# SCH_Funkypad.net
KiCad netlist of a schematic drawn in EasyEDA
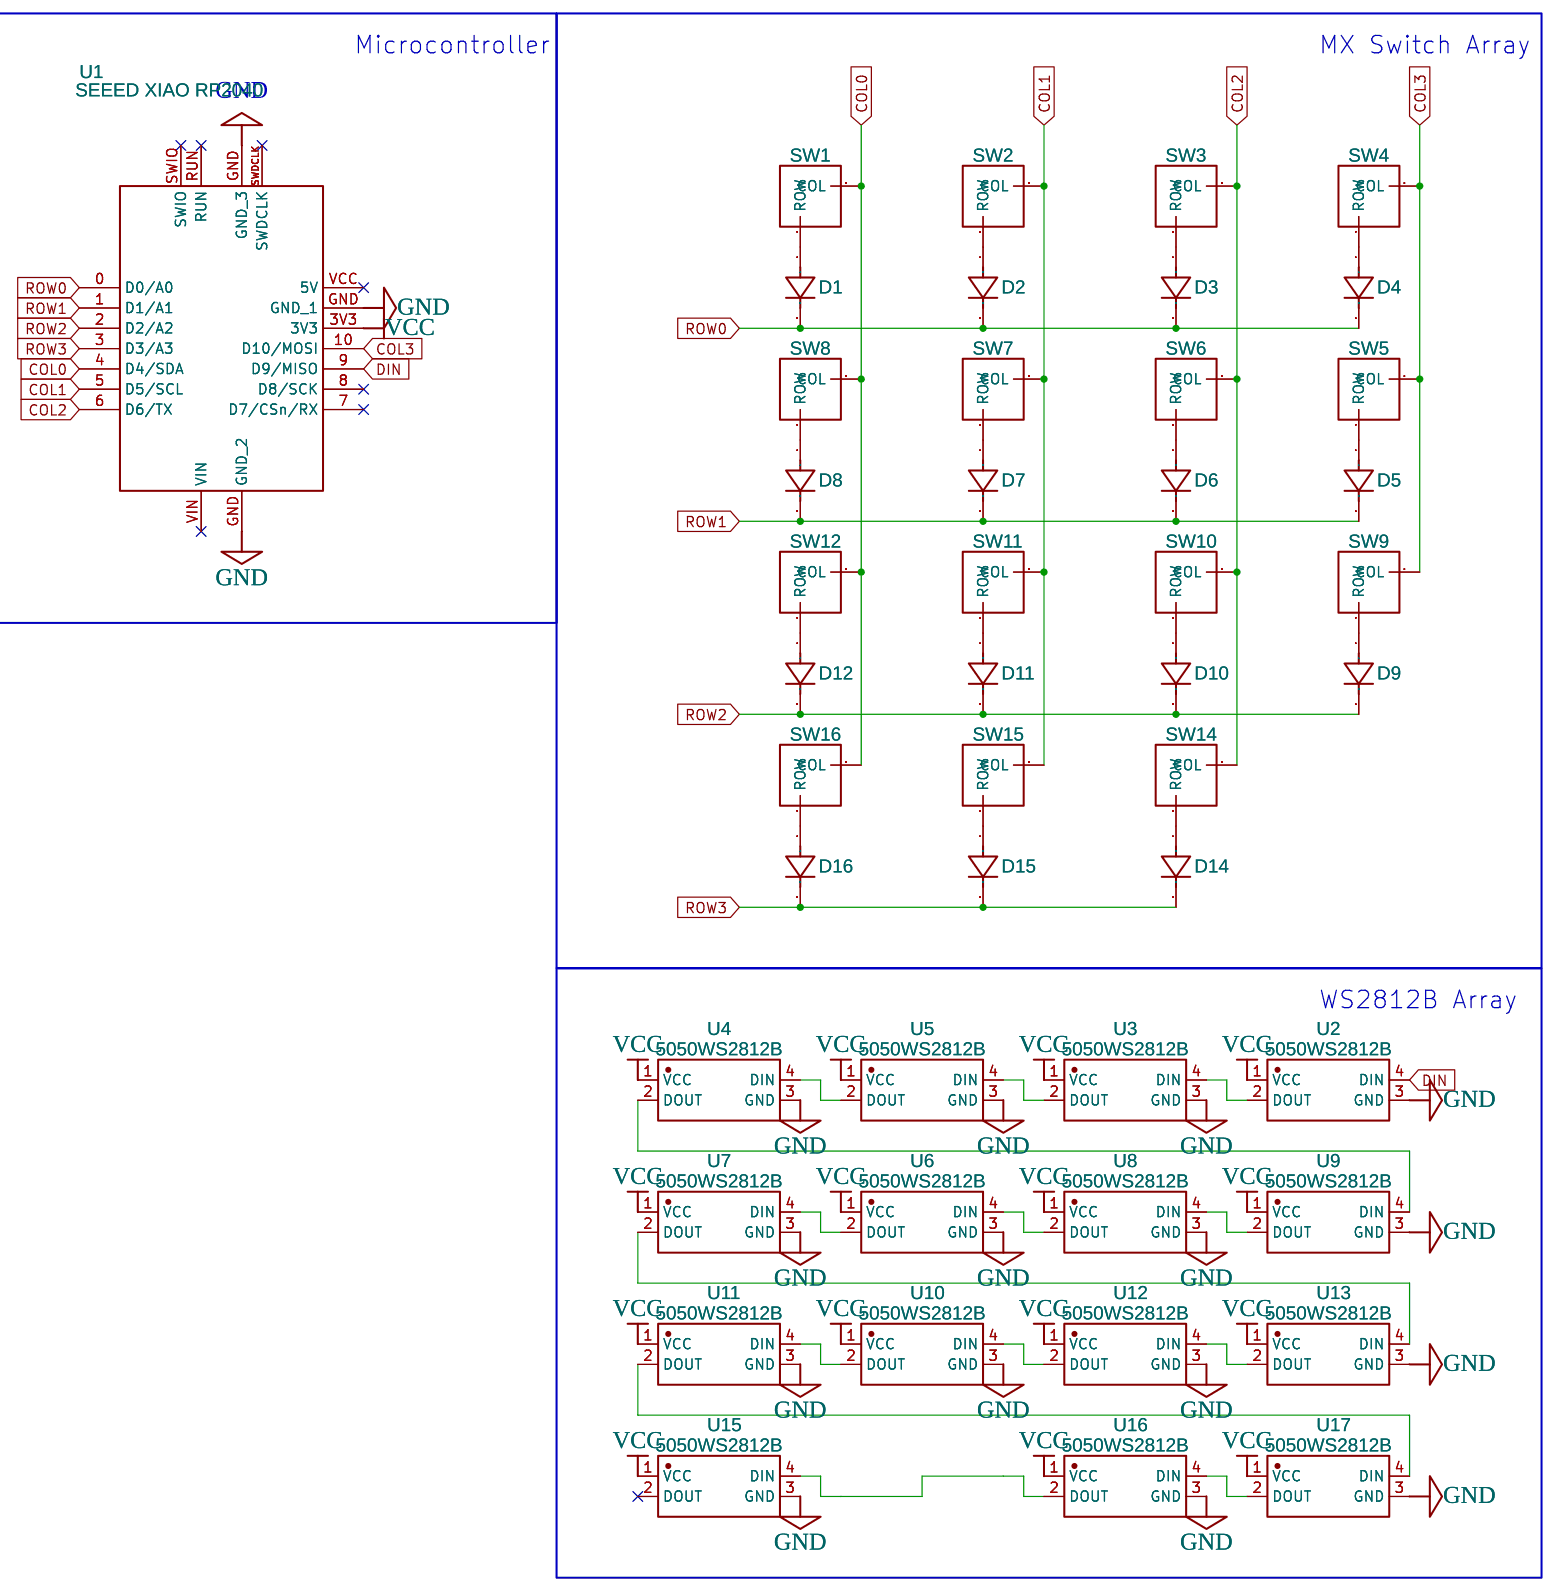
[diagram p0: schematic sheet]

(export (version "E")
  (design (tool "Eeschema 10.0.6"))
  (components
    (comp (ref "D1")
      (value "1N4148_C18195411")
      (fields (field (name "Manufacturer Part") "1N4148") (field (name "Manufacturer") "LJ(朗捷)"))
      (libsource (lib "") (part "1N4148_C18195411"))
    )
    (comp (ref "D2")
      (value "1N4148_C18195411")
      (fields (field (name "Manufacturer Part") "1N4148") (field (name "Manufacturer") "LJ(朗捷)"))
      (libsource (lib "") (part "1N4148_C18195411"))
    )
    (comp (ref "D3")
      (value "1N4148_C18195411")
      (fields (field (name "Manufacturer Part") "1N4148") (field (name "Manufacturer") "LJ(朗捷)"))
      (libsource (lib "") (part "1N4148_C18195411"))
    )
    (comp (ref "D4")
      (value "1N4148_C18195411")
      (fields (field (name "Manufacturer Part") "1N4148") (field (name "Manufacturer") "LJ(朗捷)"))
      (libsource (lib "") (part "1N4148_C18195411"))
    )
    (comp (ref "D5")
      (value "1N4148_C18195411")
      (fields (field (name "Manufacturer Part") "1N4148") (field (name "Manufacturer") "LJ(朗捷)"))
      (libsource (lib "") (part "1N4148_C18195411"))
    )
    (comp (ref "D6")
      (value "1N4148_C18195411")
      (fields (field (name "Manufacturer Part") "1N4148") (field (name "Manufacturer") "LJ(朗捷)"))
      (libsource (lib "") (part "1N4148_C18195411"))
    )
    (comp (ref "D7")
      (value "1N4148_C18195411")
      (fields (field (name "Manufacturer Part") "1N4148") (field (name "Manufacturer") "LJ(朗捷)"))
      (libsource (lib "") (part "1N4148_C18195411"))
    )
    (comp (ref "D8")
      (value "1N4148_C18195411")
      (fields (field (name "Manufacturer Part") "1N4148") (field (name "Manufacturer") "LJ(朗捷)"))
      (libsource (lib "") (part "1N4148_C18195411"))
    )
    (comp (ref "D9")
      (value "1N4148_C18195411")
      (fields (field (name "Manufacturer Part") "1N4148") (field (name "Manufacturer") "LJ(朗捷)"))
      (libsource (lib "") (part "1N4148_C18195411"))
    )
    (comp (ref "D10")
      (value "1N4148_C18195411")
      (fields (field (name "Manufacturer Part") "1N4148") (field (name "Manufacturer") "LJ(朗捷)"))
      (libsource (lib "") (part "1N4148_C18195411"))
    )
    (comp (ref "D11")
      (value "1N4148_C18195411")
      (fields (field (name "Manufacturer Part") "1N4148") (field (name "Manufacturer") "LJ(朗捷)"))
      (libsource (lib "") (part "1N4148_C18195411"))
    )
    (comp (ref "D12")
      (value "1N4148_C18195411")
      (fields (field (name "Manufacturer Part") "1N4148") (field (name "Manufacturer") "LJ(朗捷)"))
      (libsource (lib "") (part "1N4148_C18195411"))
    )
    (comp (ref "D14")
      (value "1N4148_C18195411")
      (fields (field (name "Manufacturer Part") "1N4148") (field (name "Manufacturer") "LJ(朗捷)"))
      (libsource (lib "") (part "1N4148_C18195411"))
    )
    (comp (ref "D15")
      (value "1N4148_C18195411")
      (fields (field (name "Manufacturer Part") "1N4148") (field (name "Manufacturer") "LJ(朗捷)"))
      (libsource (lib "") (part "1N4148_C18195411"))
    )
    (comp (ref "D16")
      (value "1N4148_C18195411")
      (fields (field (name "Manufacturer Part") "1N4148") (field (name "Manufacturer") "LJ(朗捷)"))
      (libsource (lib "") (part "1N4148_C18195411"))
    )
    (comp (ref "SW1")
      (value "CHERRY MX SWITCH 1.0U")
      (fields (field (name "Manufacturer Part") "Cherry"))
      (libsource (lib "") (part "CHERRY MX SWITCH 1.0U"))
    )
    (comp (ref "SW2")
      (value "CHERRY MX SWITCH 1.0U")
      (fields (field (name "Manufacturer Part") "Cherry"))
      (libsource (lib "") (part "CHERRY MX SWITCH 1.0U"))
    )
    (comp (ref "SW3")
      (value "CHERRY MX SWITCH 1.0U")
      (fields (field (name "Manufacturer Part") "Cherry"))
      (libsource (lib "") (part "CHERRY MX SWITCH 1.0U"))
    )
    (comp (ref "SW4")
      (value "CHERRY MX SWITCH 1.0U")
      (fields (field (name "Manufacturer Part") "Cherry"))
      (libsource (lib "") (part "CHERRY MX SWITCH 1.0U"))
    )
    (comp (ref "SW5")
      (value "CHERRY MX SWITCH 1.0U")
      (fields (field (name "Manufacturer Part") "Cherry"))
      (libsource (lib "") (part "CHERRY MX SWITCH 1.0U"))
    )
    (comp (ref "SW6")
      (value "CHERRY MX SWITCH 1.0U")
      (fields (field (name "Manufacturer Part") "Cherry"))
      (libsource (lib "") (part "CHERRY MX SWITCH 1.0U"))
    )
    (comp (ref "SW7")
      (value "CHERRY MX SWITCH 1.0U")
      (fields (field (name "Manufacturer Part") "Cherry"))
      (libsource (lib "") (part "CHERRY MX SWITCH 1.0U"))
    )
    (comp (ref "SW8")
      (value "CHERRY MX SWITCH 1.0U")
      (fields (field (name "Manufacturer Part") "Cherry"))
      (libsource (lib "") (part "CHERRY MX SWITCH 1.0U"))
    )
    (comp (ref "SW9")
      (value "CHERRY MX SWITCH 1.0U")
      (fields (field (name "Manufacturer Part") "Cherry"))
      (libsource (lib "") (part "CHERRY MX SWITCH 1.0U"))
    )
    (comp (ref "SW10")
      (value "CHERRY MX SWITCH 1.0U")
      (fields (field (name "Manufacturer Part") "Cherry"))
      (libsource (lib "") (part "CHERRY MX SWITCH 1.0U"))
    )
    (comp (ref "SW11")
      (value "CHERRY MX SWITCH 1.0U")
      (fields (field (name "Manufacturer Part") "Cherry"))
      (libsource (lib "") (part "CHERRY MX SWITCH 1.0U"))
    )
    (comp (ref "SW12")
      (value "CHERRY MX SWITCH 1.0U")
      (fields (field (name "Manufacturer Part") "Cherry"))
      (libsource (lib "") (part "CHERRY MX SWITCH 1.0U"))
    )
    (comp (ref "SW14")
      (value "CHERRY MX SWITCH 1.0U")
      (fields (field (name "Manufacturer Part") "Cherry"))
      (libsource (lib "") (part "CHERRY MX SWITCH 1.0U"))
    )
    (comp (ref "SW15")
      (value "CHERRY MX SWITCH 1.0U")
      (fields (field (name "Manufacturer Part") "Cherry"))
      (libsource (lib "") (part "CHERRY MX SWITCH 1.0U"))
    )
    (comp (ref "SW16")
      (value "CHERRY MX SWITCH 1.0U")
      (fields (field (name "Manufacturer Part") "Cherry"))
      (libsource (lib "") (part "CHERRY MX SWITCH 1.0U"))
    )
    (comp (ref "U1") (value "SEEED XIAO RP2040") (libsource (lib "") (part "SEEED XIAO RP2040")))
    (comp (ref "U2") (value "5050WS2812B") (libsource (lib "") (part "5050WS2812B")))
    (comp (ref "U3") (value "5050WS2812B") (libsource (lib "") (part "5050WS2812B")))
    (comp (ref "U4") (value "5050WS2812B") (libsource (lib "") (part "5050WS2812B")))
    (comp (ref "U5") (value "5050WS2812B") (libsource (lib "") (part "5050WS2812B")))
    (comp (ref "U6") (value "5050WS2812B") (libsource (lib "") (part "5050WS2812B")))
    (comp (ref "U7") (value "5050WS2812B") (libsource (lib "") (part "5050WS2812B")))
    (comp (ref "U8") (value "5050WS2812B") (libsource (lib "") (part "5050WS2812B")))
    (comp (ref "U9") (value "5050WS2812B") (libsource (lib "") (part "5050WS2812B")))
    (comp (ref "U10") (value "5050WS2812B") (libsource (lib "") (part "5050WS2812B")))
    (comp (ref "U11") (value "5050WS2812B") (libsource (lib "") (part "5050WS2812B")))
    (comp (ref "U12") (value "5050WS2812B") (libsource (lib "") (part "5050WS2812B")))
    (comp (ref "U13") (value "5050WS2812B") (libsource (lib "") (part "5050WS2812B")))
    (comp (ref "U15") (value "5050WS2812B") (libsource (lib "") (part "5050WS2812B")))
    (comp (ref "U16") (value "5050WS2812B") (libsource (lib "") (part "5050WS2812B")))
    (comp (ref "U17") (value "5050WS2812B") (libsource (lib "") (part "5050WS2812B")))
  )
  (nets
    (net (code "1") (name "COL0") (class "Default")
      (node (ref "SW1") (pin "C") (pinfunction "COL_C") (pintype "unspecified"))
      (node (ref "SW12") (pin "C") (pinfunction "COL_C") (pintype "unspecified"))
      (node (ref "SW16") (pin "C") (pinfunction "COL_C") (pintype "unspecified"))
      (node (ref "SW8") (pin "C") (pinfunction "COL_C") (pintype "unspecified"))
      (node (ref "U1") (pin "4") (pinfunction "D4/SDA_4") (pintype "unspecified"))
    )
    (net (code "2") (name "COL1") (class "Default")
      (node (ref "SW11") (pin "C") (pinfunction "COL_C") (pintype "unspecified"))
      (node (ref "SW15") (pin "C") (pinfunction "COL_C") (pintype "unspecified"))
      (node (ref "SW2") (pin "C") (pinfunction "COL_C") (pintype "unspecified"))
      (node (ref "SW7") (pin "C") (pinfunction "COL_C") (pintype "unspecified"))
      (node (ref "U1") (pin "5") (pinfunction "D5/SCL_5") (pintype "unspecified"))
    )
    (net (code "3") (name "COL2") (class "Default")
      (node (ref "SW10") (pin "C") (pinfunction "COL_C") (pintype "unspecified"))
      (node (ref "SW14") (pin "C") (pinfunction "COL_C") (pintype "unspecified"))
      (node (ref "SW3") (pin "C") (pinfunction "COL_C") (pintype "unspecified"))
      (node (ref "SW6") (pin "C") (pinfunction "COL_C") (pintype "unspecified"))
      (node (ref "U1") (pin "6") (pinfunction "D6/TX_6") (pintype "unspecified"))
    )
    (net (code "4") (name "COL3") (class "Default")
      (node (ref "SW4") (pin "C") (pinfunction "COL_C") (pintype "unspecified"))
      (node (ref "SW5") (pin "C") (pinfunction "COL_C") (pintype "unspecified"))
      (node (ref "SW9") (pin "C") (pinfunction "COL_C") (pintype "unspecified"))
      (node (ref "U1") (pin "10") (pinfunction "D10/MOSI_10") (pintype "unspecified"))
    )
    (net (code "5") (name "DIN") (class "Default")
      (node (ref "U1") (pin "9") (pinfunction "D9/MISO_9") (pintype "unspecified"))
      (node (ref "U2") (pin "4") (pinfunction "DIN_4") (pintype "unspecified"))
    )
    (net (code "6") (name "GND") (class "Default")
      (node (ref "U1") (pin "GND") (pinfunction "GND_2_GND") (pintype "unspecified"))
      (node (ref "U10") (pin "3") (pinfunction "GND_3") (pintype "unspecified"))
      (node (ref "U11") (pin "3") (pinfunction "GND_3") (pintype "unspecified"))
      (node (ref "U12") (pin "3") (pinfunction "GND_3") (pintype "unspecified"))
      (node (ref "U13") (pin "3") (pinfunction "GND_3") (pintype "unspecified"))
      (node (ref "U15") (pin "3") (pinfunction "GND_3") (pintype "unspecified"))
      (node (ref "U16") (pin "3") (pinfunction "GND_3") (pintype "unspecified"))
      (node (ref "U17") (pin "3") (pinfunction "GND_3") (pintype "unspecified"))
      (node (ref "U2") (pin "3") (pinfunction "GND_3") (pintype "unspecified"))
      (node (ref "U3") (pin "3") (pinfunction "GND_3") (pintype "unspecified"))
      (node (ref "U4") (pin "3") (pinfunction "GND_3") (pintype "unspecified"))
      (node (ref "U5") (pin "3") (pinfunction "GND_3") (pintype "unspecified"))
      (node (ref "U6") (pin "3") (pinfunction "GND_3") (pintype "unspecified"))
      (node (ref "U7") (pin "3") (pinfunction "GND_3") (pintype "unspecified"))
      (node (ref "U8") (pin "3") (pinfunction "GND_3") (pintype "unspecified"))
      (node (ref "U9") (pin "3") (pinfunction "GND_3") (pintype "unspecified"))
    )
    (net (code "7") (name "Net-(D1-A)") (class "Default")
      (node (ref "D1") (pin "1") (pinfunction "A_1") (pintype "unspecified"))
      (node (ref "SW1") (pin "R") (pinfunction "ROW_R") (pintype "unspecified"))
    )
    (net (code "8") (name "Net-(D2-A)") (class "Default")
      (node (ref "D2") (pin "1") (pinfunction "A_1") (pintype "unspecified"))
      (node (ref "SW2") (pin "R") (pinfunction "ROW_R") (pintype "unspecified"))
    )
    (net (code "9") (name "Net-(D3-A)") (class "Default")
      (node (ref "D3") (pin "1") (pinfunction "A_1") (pintype "unspecified"))
      (node (ref "SW3") (pin "R") (pinfunction "ROW_R") (pintype "unspecified"))
    )
    (net (code "10") (name "Net-(D4-A)") (class "Default")
      (node (ref "D4") (pin "1") (pinfunction "A_1") (pintype "unspecified"))
      (node (ref "SW4") (pin "R") (pinfunction "ROW_R") (pintype "unspecified"))
    )
    (net (code "11") (name "Net-(D5-A)") (class "Default")
      (node (ref "D5") (pin "1") (pinfunction "A_1") (pintype "unspecified"))
      (node (ref "SW5") (pin "R") (pinfunction "ROW_R") (pintype "unspecified"))
    )
    (net (code "12") (name "Net-(D6-A)") (class "Default")
      (node (ref "D6") (pin "1") (pinfunction "A_1") (pintype "unspecified"))
      (node (ref "SW6") (pin "R") (pinfunction "ROW_R") (pintype "unspecified"))
    )
    (net (code "13") (name "Net-(D7-A)") (class "Default")
      (node (ref "D7") (pin "1") (pinfunction "A_1") (pintype "unspecified"))
      (node (ref "SW7") (pin "R") (pinfunction "ROW_R") (pintype "unspecified"))
    )
    (net (code "14") (name "Net-(D8-A)") (class "Default")
      (node (ref "D8") (pin "1") (pinfunction "A_1") (pintype "unspecified"))
      (node (ref "SW8") (pin "R") (pinfunction "ROW_R") (pintype "unspecified"))
    )
    (net (code "15") (name "Net-(D9-A)") (class "Default")
      (node (ref "D9") (pin "1") (pinfunction "A_1") (pintype "unspecified"))
      (node (ref "SW9") (pin "R") (pinfunction "ROW_R") (pintype "unspecified"))
    )
    (net (code "16") (name "Net-(D10-A)") (class "Default")
      (node (ref "D10") (pin "1") (pinfunction "A_1") (pintype "unspecified"))
      (node (ref "SW10") (pin "R") (pinfunction "ROW_R") (pintype "unspecified"))
    )
    (net (code "17") (name "Net-(D11-A)") (class "Default")
      (node (ref "D11") (pin "1") (pinfunction "A_1") (pintype "unspecified"))
      (node (ref "SW11") (pin "R") (pinfunction "ROW_R") (pintype "unspecified"))
    )
    (net (code "18") (name "Net-(D12-A)") (class "Default")
      (node (ref "D12") (pin "1") (pinfunction "A_1") (pintype "unspecified"))
      (node (ref "SW12") (pin "R") (pinfunction "ROW_R") (pintype "unspecified"))
    )
    (net (code "19") (name "Net-(D14-A)") (class "Default")
      (node (ref "D14") (pin "1") (pinfunction "A_1") (pintype "unspecified"))
      (node (ref "SW14") (pin "R") (pinfunction "ROW_R") (pintype "unspecified"))
    )
    (net (code "20") (name "Net-(D15-A)") (class "Default")
      (node (ref "D15") (pin "1") (pinfunction "A_1") (pintype "unspecified"))
      (node (ref "SW15") (pin "R") (pinfunction "ROW_R") (pintype "unspecified"))
    )
    (net (code "21") (name "Net-(D16-A)") (class "Default")
      (node (ref "D16") (pin "1") (pinfunction "A_1") (pintype "unspecified"))
      (node (ref "SW16") (pin "R") (pinfunction "ROW_R") (pintype "unspecified"))
    )
    (net (code "22") (name "Net-(U2-DOUT)") (class "Default")
      (node (ref "U2") (pin "2") (pinfunction "DOUT_2") (pintype "unspecified"))
      (node (ref "U3") (pin "4") (pinfunction "DIN_4") (pintype "unspecified"))
    )
    (net (code "23") (name "Net-(U3-DOUT)") (class "Default")
      (node (ref "U3") (pin "2") (pinfunction "DOUT_2") (pintype "unspecified"))
      (node (ref "U5") (pin "4") (pinfunction "DIN_4") (pintype "unspecified"))
    )
    (net (code "24") (name "Net-(U4-DIN)") (class "Default")
      (node (ref "U4") (pin "4") (pinfunction "DIN_4") (pintype "unspecified"))
      (node (ref "U5") (pin "2") (pinfunction "DOUT_2") (pintype "unspecified"))
    )
    (net (code "25") (name "Net-(U4-DOUT)") (class "Default")
      (node (ref "U4") (pin "2") (pinfunction "DOUT_2") (pintype "unspecified"))
      (node (ref "U9") (pin "4") (pinfunction "DIN_4") (pintype "unspecified"))
    )
    (net (code "26") (name "Net-(U6-DIN)") (class "Default")
      (node (ref "U6") (pin "4") (pinfunction "DIN_4") (pintype "unspecified"))
      (node (ref "U8") (pin "2") (pinfunction "DOUT_2") (pintype "unspecified"))
    )
    (net (code "27") (name "Net-(U6-DOUT)") (class "Default")
      (node (ref "U6") (pin "2") (pinfunction "DOUT_2") (pintype "unspecified"))
      (node (ref "U7") (pin "4") (pinfunction "DIN_4") (pintype "unspecified"))
    )
    (net (code "28") (name "Net-(U8-DIN)") (class "Default")
      (node (ref "U8") (pin "4") (pinfunction "DIN_4") (pintype "unspecified"))
      (node (ref "U9") (pin "2") (pinfunction "DOUT_2") (pintype "unspecified"))
    )
    (net (code "29") (name "Net-(U10-DIN)") (class "Default")
      (node (ref "U10") (pin "4") (pinfunction "DIN_4") (pintype "unspecified"))
      (node (ref "U12") (pin "2") (pinfunction "DOUT_2") (pintype "unspecified"))
    )
    (net (code "30") (name "Net-(U10-DOUT)") (class "Default")
      (node (ref "U10") (pin "2") (pinfunction "DOUT_2") (pintype "unspecified"))
      (node (ref "U11") (pin "4") (pinfunction "DIN_4") (pintype "unspecified"))
    )
    (net (code "31") (name "Net-(U11-DOUT)") (class "Default")
      (node (ref "U11") (pin "2") (pinfunction "DOUT_2") (pintype "unspecified"))
      (node (ref "U17") (pin "4") (pinfunction "DIN_4") (pintype "unspecified"))
    )
    (net (code "32") (name "Net-(U12-DIN)") (class "Default")
      (node (ref "U12") (pin "4") (pinfunction "DIN_4") (pintype "unspecified"))
      (node (ref "U13") (pin "2") (pinfunction "DOUT_2") (pintype "unspecified"))
    )
    (net (code "33") (name "Net-(U13-DIN)") (class "Default")
      (node (ref "U13") (pin "4") (pinfunction "DIN_4") (pintype "unspecified"))
      (node (ref "U7") (pin "2") (pinfunction "DOUT_2") (pintype "unspecified"))
    )
    (net (code "34") (name "Net-(U15-DIN)") (class "Default")
      (node (ref "U15") (pin "4") (pinfunction "DIN_4") (pintype "unspecified"))
      (node (ref "U16") (pin "2") (pinfunction "DOUT_2") (pintype "unspecified"))
    )
    (net (code "35") (name "Net-(U16-DIN)") (class "Default")
      (node (ref "U16") (pin "4") (pinfunction "DIN_4") (pintype "unspecified"))
      (node (ref "U17") (pin "2") (pinfunction "DOUT_2") (pintype "unspecified"))
    )
    (net (code "36") (name "ROW0") (class "Default")
      (node (ref "D1") (pin "2") (pinfunction "C_2") (pintype "unspecified"))
      (node (ref "D2") (pin "2") (pinfunction "C_2") (pintype "unspecified"))
      (node (ref "D3") (pin "2") (pinfunction "C_2") (pintype "unspecified"))
      (node (ref "D4") (pin "2") (pinfunction "C_2") (pintype "unspecified"))
      (node (ref "U1") (pin "0") (pinfunction "D0/A0_0") (pintype "unspecified"))
    )
    (net (code "37") (name "ROW1") (class "Default")
      (node (ref "D5") (pin "2") (pinfunction "C_2") (pintype "unspecified"))
      (node (ref "D6") (pin "2") (pinfunction "C_2") (pintype "unspecified"))
      (node (ref "D7") (pin "2") (pinfunction "C_2") (pintype "unspecified"))
      (node (ref "D8") (pin "2") (pinfunction "C_2") (pintype "unspecified"))
      (node (ref "U1") (pin "1") (pinfunction "D1/A1_1") (pintype "unspecified"))
    )
    (net (code "38") (name "ROW2") (class "Default")
      (node (ref "D10") (pin "2") (pinfunction "C_2") (pintype "unspecified"))
      (node (ref "D11") (pin "2") (pinfunction "C_2") (pintype "unspecified"))
      (node (ref "D12") (pin "2") (pinfunction "C_2") (pintype "unspecified"))
      (node (ref "D9") (pin "2") (pinfunction "C_2") (pintype "unspecified"))
      (node (ref "U1") (pin "2") (pinfunction "D2/A2_2") (pintype "unspecified"))
    )
    (net (code "39") (name "ROW3") (class "Default")
      (node (ref "D14") (pin "2") (pinfunction "C_2") (pintype "unspecified"))
      (node (ref "D15") (pin "2") (pinfunction "C_2") (pintype "unspecified"))
      (node (ref "D16") (pin "2") (pinfunction "C_2") (pintype "unspecified"))
      (node (ref "U1") (pin "3") (pinfunction "D3/A3_3") (pintype "unspecified"))
    )
    (net (code "40") (name "VCC") (class "Default")
      (node (ref "U1") (pin "3V3") (pinfunction "3V3_3V3") (pintype "unspecified"))
      (node (ref "U10") (pin "1") (pinfunction "VCC_1") (pintype "unspecified"))
      (node (ref "U11") (pin "1") (pinfunction "VCC_1") (pintype "unspecified"))
      (node (ref "U12") (pin "1") (pinfunction "VCC_1") (pintype "unspecified"))
      (node (ref "U13") (pin "1") (pinfunction "VCC_1") (pintype "unspecified"))
      (node (ref "U15") (pin "1") (pinfunction "VCC_1") (pintype "unspecified"))
      (node (ref "U16") (pin "1") (pinfunction "VCC_1") (pintype "unspecified"))
      (node (ref "U17") (pin "1") (pinfunction "VCC_1") (pintype "unspecified"))
      (node (ref "U2") (pin "1") (pinfunction "VCC_1") (pintype "unspecified"))
      (node (ref "U3") (pin "1") (pinfunction "VCC_1") (pintype "unspecified"))
      (node (ref "U4") (pin "1") (pinfunction "VCC_1") (pintype "unspecified"))
      (node (ref "U5") (pin "1") (pinfunction "VCC_1") (pintype "unspecified"))
      (node (ref "U6") (pin "1") (pinfunction "VCC_1") (pintype "unspecified"))
      (node (ref "U7") (pin "1") (pinfunction "VCC_1") (pintype "unspecified"))
      (node (ref "U8") (pin "1") (pinfunction "VCC_1") (pintype "unspecified"))
      (node (ref "U9") (pin "1") (pinfunction "VCC_1") (pintype "unspecified"))
    )
    (net (code "41") (name "unconnected-(U1-5V-PadVCC)") (class "Default")
      (node (ref "U1") (pin "VCC") (pinfunction "5V_VCC") (pintype "unspecified+no_connect"))
    )
    (net (code "42") (name "unconnected-(U1-D7{slash}CSn{slash}RX-Pad7)") (class "Default")
      (node (ref "U1") (pin "7") (pinfunction "D7/CSn/RX_7") (pintype "unspecified+no_connect"))
    )
    (net (code "43") (name "unconnected-(U1-D8{slash}SCK-Pad8)") (class "Default")
      (node (ref "U1") (pin "8") (pinfunction "D8/SCK_8") (pintype "unspecified+no_connect"))
    )
    (net (code "44") (name "unconnected-(U1-PadRUN)") (class "Default")
      (node (ref "U1") (pin "RUN") (pinfunction "RUN_RUN") (pintype "unspecified+no_connect"))
    )
    (net (code "45") (name "unconnected-(U1-PadSWDCLK)") (class "Default")
      (node (ref "U1") (pin "SWDCLK") (pinfunction "SWDCLK_SWDCLK") (pintype "unspecified+no_connect"))
    )
    (net (code "46") (name "unconnected-(U1-PadSWIO)") (class "Default")
      (node (ref "U1") (pin "SWIO") (pinfunction "SWIO_SWIO") (pintype "unspecified+no_connect"))
    )
    (net (code "47") (name "unconnected-(U1-PadVIN)") (class "Default")
      (node (ref "U1") (pin "VIN") (pinfunction "VIN_VIN") (pintype "unspecified+no_connect"))
    )
    (net (code "48") (name "unconnected-(U15-DOUT-Pad2)") (class "Default")
      (node (ref "U15") (pin "2") (pinfunction "DOUT_2") (pintype "unspecified+no_connect"))
    )
  )
)
